# Power_supply.net
KiCad netlist of a schematic drawn in Altium Designer
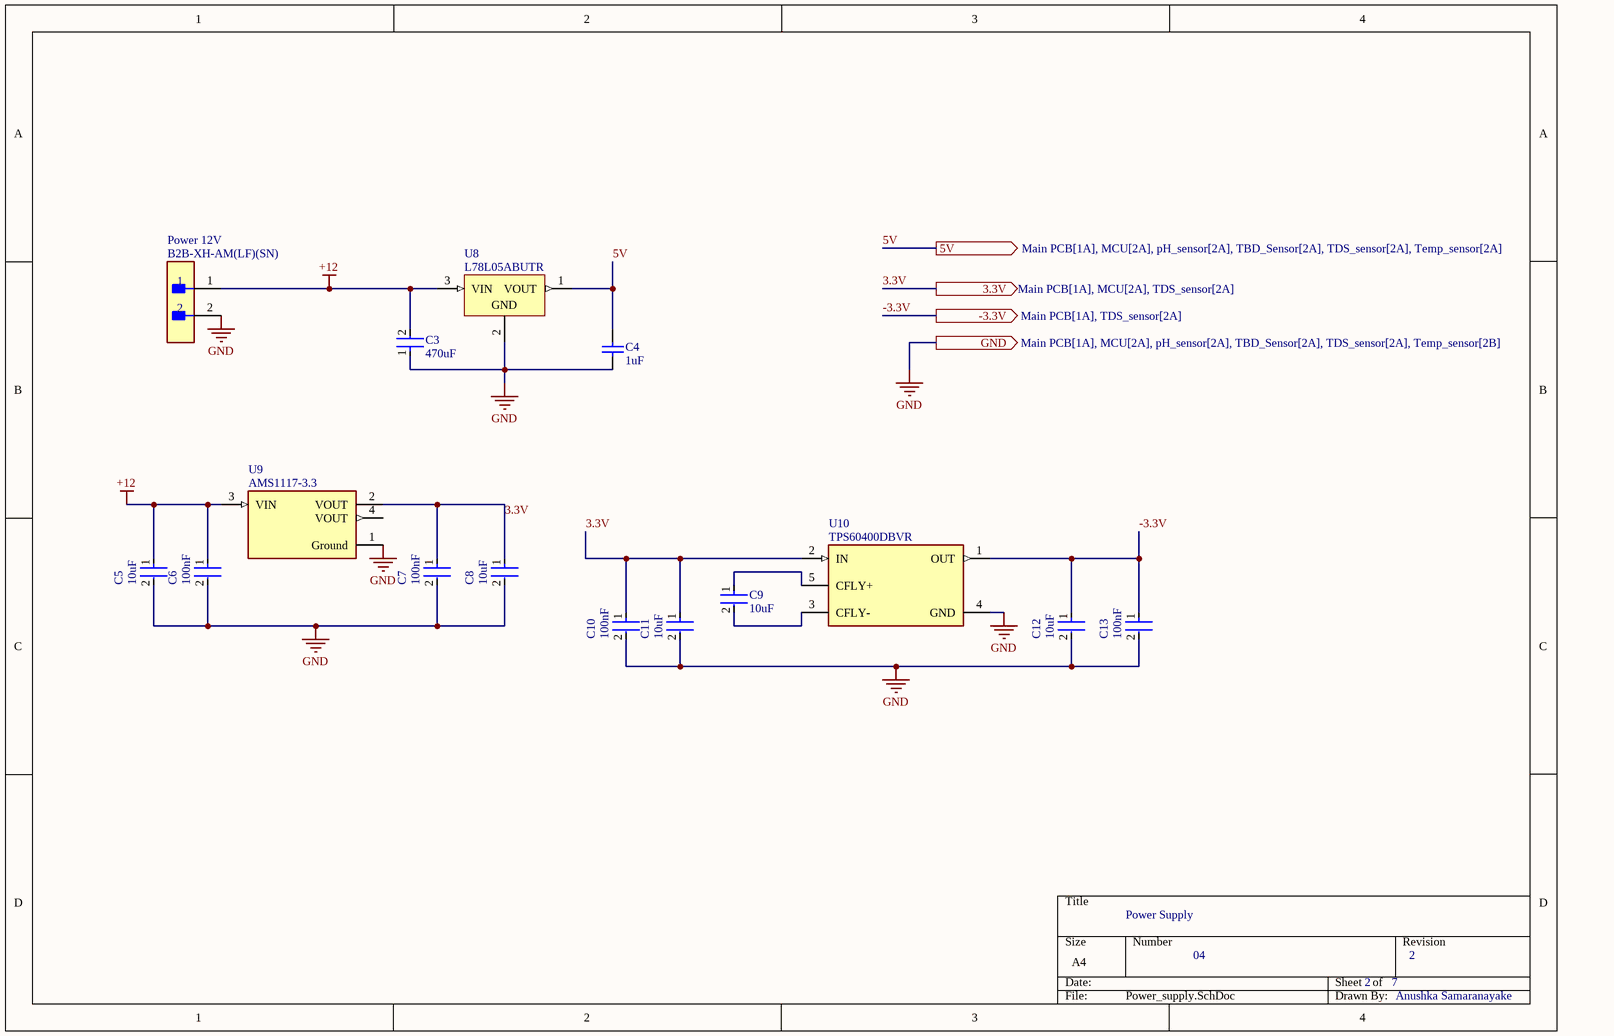
[diagram p0: Power_supply.SchDoc]

(export (version "E")
  (design (tool "Eeschema 10.0.6"))
  (components
    (comp (ref "C3")
      (value "470uF")
      (footprint "FP-CL31-IPC_B")
      (description "Cap Ceramic 100nF 50V X7R ±10% SMD 1206 +125°C Embossed T/R")
      (fields (field (name "VOLTAGE") "50V") (field (name "TOLERANCE") "10%"))
      (libsource (lib "Altium Content Vault") (part "b4654b650e69147ec39a6b967a45e02"))
    )
    (comp (ref "C4")
      (value "1uF")
      (footprint "CAPC2013X135X50LL15T20")
      (fields (field (name "MANUFACTURER") "Vitramon") (field (name "PART NUMBER") "VJ0805Y102KXACW1BC"))
      (libsource (lib "Altium Content Vault") (part "CAP"))
    )
    (comp (ref "C5")
      (value "10uF")
      (footprint "FP-CL31-IPC_B")
      (description "Cap Ceramic 100nF 50V X7R ±10% SMD 1206 +125°C Embossed T/R")
      (fields (field (name "VOLTAGE") "50V") (field (name "TOLERANCE") "10%"))
      (libsource (lib "Altium Content Vault") (part "b4654b650e69147ec39a6b967a45e02"))
    )
    (comp (ref "C6")
      (value "100nF")
      (footprint "FP-CL31-IPC_B")
      (description "Cap Ceramic 100nF 50V X7R ±10% SMD 1206 +125°C Embossed T/R")
      (fields (field (name "VOLTAGE") "50V") (field (name "TOLERANCE") "10%"))
      (libsource (lib "Altium Content Vault") (part "b4654b650e69147ec39a6b967a45e02"))
    )
    (comp (ref "C7")
      (value "100nF")
      (footprint "FP-CL31-IPC_B")
      (description "Cap Ceramic 100nF 50V X7R ±10% SMD 1206 +125°C Embossed T/R")
      (fields (field (name "VOLTAGE") "50V") (field (name "TOLERANCE") "10%"))
      (libsource (lib "Altium Content Vault") (part "b4654b650e69147ec39a6b967a45e02"))
    )
    (comp (ref "C8")
      (value "10uF")
      (footprint "FP-CL31-IPC_B")
      (description "Cap Ceramic 100nF 50V X7R ±10% SMD 1206 +125°C Embossed T/R")
      (fields (field (name "VOLTAGE") "50V") (field (name "TOLERANCE") "10%"))
      (libsource (lib "Altium Content Vault") (part "b4654b650e69147ec39a6b967a45e02"))
    )
    (comp (ref "C9")
      (value "10uF")
      (footprint "FP-CL31-IPC_B")
      (description "Cap Ceramic 100nF 50V X7R ±10% SMD 1206 +125°C Embossed T/R")
      (fields (field (name "VOLTAGE") "50V") (field (name "TOLERANCE") "10%"))
      (libsource (lib "Altium Content Vault") (part "b4654b650e69147ec39a6b967a45e02"))
    )
    (comp (ref "C10")
      (value "100nF")
      (footprint "FP-CL31-IPC_B")
      (description "Cap Ceramic 100nF 50V X7R ±10% SMD 1206 +125°C Embossed T/R")
      (fields (field (name "VOLTAGE") "50V") (field (name "TOLERANCE") "10%"))
      (libsource (lib "Altium Content Vault") (part "b4654b650e69147ec39a6b967a45e02"))
    )
    (comp (ref "C11")
      (value "10uF")
      (footprint "FP-CL31-IPC_B")
      (description "Cap Ceramic 100nF 50V X7R ±10% SMD 1206 +125°C Embossed T/R")
      (fields (field (name "VOLTAGE") "50V") (field (name "TOLERANCE") "10%"))
      (libsource (lib "Altium Content Vault") (part "b4654b650e69147ec39a6b967a45e02"))
    )
    (comp (ref "C12")
      (value "10uF")
      (footprint "FP-CL31-IPC_B")
      (description "Cap Ceramic 100nF 50V X7R ±10% SMD 1206 +125°C Embossed T/R")
      (fields (field (name "VOLTAGE") "50V") (field (name "TOLERANCE") "10%"))
      (libsource (lib "Altium Content Vault") (part "b4654b650e69147ec39a6b967a45e02"))
    )
    (comp (ref "C13")
      (value "100nF")
      (footprint "FP-CL31-IPC_B")
      (description "Cap Ceramic 100nF 50V X7R ±10% SMD 1206 +125°C Embossed T/R")
      (fields (field (name "VOLTAGE") "50V") (field (name "TOLERANCE") "10%"))
      (libsource (lib "Altium Content Vault") (part "b4654b650e69147ec39a6b967a45e02"))
    )
    (comp (ref "Power 12V")
      (value "B2B-XH-AM(LF)(SN)")
      (footprint "FP-B2B-XH-AM_LF_SN-MFG")
      (description "CONN HEADER VERT 2POS 2.5MM")
      (libsource (lib "Altium Content Vault") (part "3bc925449376181038e59eaffc5286c"))
    )
    (comp (ref "U8")
      (value "L78L05ABUTR")
      (footprint "SOT-89_N")
      (description "Positive Voltage Regulator, 5V, 4-Pin SOT-89, Tape and Reel")
      (libsource (lib "Altium Content Vault") (part "PM-REG-7805-SIL3"))
    )
    (comp (ref "U9")
      (value "AMS1117-3.3")
      (footprint "FP-AMS1117-IPC_C")
      (description "LDO Voltage Regulators 1A, 3.3V")
      (fields
        (field (name "OCTOPART") "https://octopart.com/ams1117-3.3-advanced+monolithic+systems-25899300")
        (field (name "MANUFACTURER") "Advanced Monolithic Systems")
      )
      (libsource (lib "Altium Content Vault") (part "8bdbb5f8e77002000e30dd2845d0354"))
    )
    (comp (ref "U10")
      (value "TPS60400DBVR")
      (footprint "FP-DBV0005A-IPC_B")
      (description "IC REG CHARG PUMP INV 60MA SOT23")
      (libsource (lib "Altium Content Vault") (part "027376aeb0d6df1338393bd3c828556"))
    )
  )
  (nets
    (net (code "1") (name "+12") (class "Default")
      (node (ref "C3") (pin "2") (pinfunction "2_2") (pintype "passive"))
      (node (ref "C5") (pin "1") (pinfunction "1_1") (pintype "passive"))
      (node (ref "C6") (pin "1") (pinfunction "1_1") (pintype "passive"))
      (node (ref "Power 12V") (pin "1") (pinfunction "1_1") (pintype "passive"))
      (node (ref "U8") (pin "3") (pinfunction "VIN_3") (pintype "input"))
      (node (ref "U9") (pin "3") (pinfunction "VIN_3") (pintype "input"))
    )
    (net (code "2") (name "/-3.3V") (class "Default")
      (node (ref "C12") (pin "1") (pinfunction "1_1") (pintype "passive"))
      (node (ref "C13") (pin "1") (pinfunction "1_1") (pintype "passive"))
      (node (ref "U10") (pin "1") (pinfunction "OUT_1") (pintype "output"))
    )
    (net (code "3") (name "/3.3V") (class "Default")
      (node (ref "C10") (pin "1") (pinfunction "1_1") (pintype "passive"))
      (node (ref "C11") (pin "1") (pinfunction "1_1") (pintype "passive"))
      (node (ref "C7") (pin "1") (pinfunction "1_1") (pintype "passive"))
      (node (ref "C8") (pin "1") (pinfunction "1_1") (pintype "passive"))
      (node (ref "U10") (pin "2") (pinfunction "IN_2") (pintype "input"))
      (node (ref "U9") (pin "2") (pinfunction "VOUT_2") (pintype "passive"))
    )
    (net (code "4") (name "/5V") (class "Default")
      (node (ref "C4") (pin "2") (pinfunction "2_2") (pintype "passive"))
      (node (ref "U8") (pin "1") (pinfunction "VOUT_1") (pintype "output"))
    )
    (net (code "5") (name "GND") (class "Default")
      (node (ref "C10") (pin "2") (pinfunction "2_2") (pintype "passive"))
      (node (ref "C11") (pin "2") (pinfunction "2_2") (pintype "passive"))
      (node (ref "C12") (pin "2") (pinfunction "2_2") (pintype "passive"))
      (node (ref "C13") (pin "2") (pinfunction "2_2") (pintype "passive"))
      (node (ref "C3") (pin "1") (pinfunction "1_1") (pintype "passive"))
      (node (ref "C4") (pin "1") (pinfunction "1_1") (pintype "passive"))
      (node (ref "C5") (pin "2") (pinfunction "2_2") (pintype "passive"))
      (node (ref "C6") (pin "2") (pinfunction "2_2") (pintype "passive"))
      (node (ref "C7") (pin "2") (pinfunction "2_2") (pintype "passive"))
      (node (ref "C8") (pin "2") (pinfunction "2_2") (pintype "passive"))
      (node (ref "Power 12V") (pin "2") (pinfunction "2_2") (pintype "passive"))
      (node (ref "U10") (pin "4") (pinfunction "GND_4") (pintype "passive"))
      (node (ref "U8") (pin "2") (pinfunction "GND_2") (pintype "passive"))
      (node (ref "U9") (pin "1") (pinfunction "Ground_1") (pintype "passive"))
    )
    (net (code "6") (name "Net-(U10-CFLY+)") (class "Default")
      (node (ref "C9") (pin "1") (pinfunction "1_1") (pintype "passive"))
      (node (ref "U10") (pin "5") (pinfunction "CFLY+_5") (pintype "passive"))
    )
    (net (code "7") (name "Net-(U10-CFLY-)") (class "Default")
      (node (ref "C9") (pin "2") (pinfunction "2_2") (pintype "passive"))
      (node (ref "U10") (pin "3") (pinfunction "CFLY-_3") (pintype "passive"))
    )
    (net (code "8") (name "unconnected-(U9-VOUT-Pad4)") (class "Default")
      (node (ref "U9") (pin "4") (pinfunction "VOUT_4") (pintype "output"))
    )
  )
)
